# dc_dc_2.net
KiCad netlist of a schematic drawn in EAGLE
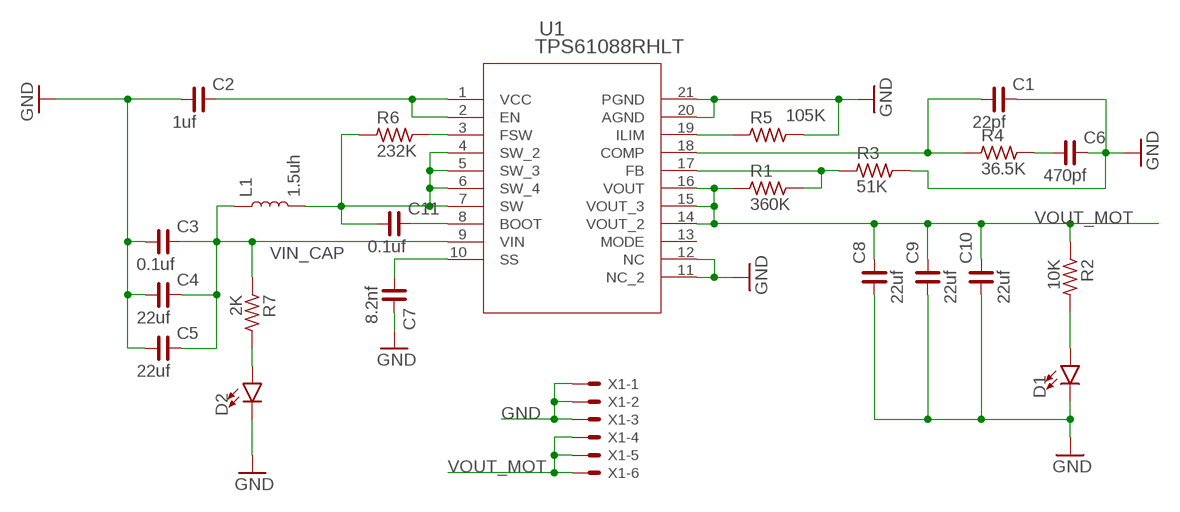
[diagram p0: schematic, sheet 1]

(export (version "E")
  (design (tool "Eeschema 10.0.6"))
  (components
    (comp (ref "C1")
      (value "22pf")
      (footprint "eagle-import:C0603")
      (libsource (lib "eagle-import") (part "C_0603"))
    )
    (comp (ref "C2")
      (value "1uf")
      (footprint "eagle-import:C0603")
      (libsource (lib "eagle-import") (part "C_0603"))
    )
    (comp (ref "C3")
      (value "0.1uf")
      (footprint "eagle-import:C1210")
      (libsource (lib "eagle-import") (part "C_1210"))
    )
    (comp (ref "C4")
      (value "22uf")
      (footprint "eagle-import:C1210")
      (libsource (lib "eagle-import") (part "C_1210"))
    )
    (comp (ref "C5")
      (value "22uf")
      (footprint "eagle-import:C1210")
      (libsource (lib "eagle-import") (part "C_1210"))
    )
    (comp (ref "C6")
      (value "470pf")
      (footprint "eagle-import:C0603")
      (libsource (lib "eagle-import") (part "C_0603"))
    )
    (comp (ref "C7")
      (value "8.2nf")
      (footprint "eagle-import:C0603")
      (libsource (lib "eagle-import") (part "C_0603"))
    )
    (comp (ref "C8")
      (value "22uf")
      (footprint "eagle-import:C1210")
      (libsource (lib "eagle-import") (part "C_1210"))
    )
    (comp (ref "C9")
      (value "22uf")
      (footprint "eagle-import:C1210")
      (libsource (lib "eagle-import") (part "C_1210"))
    )
    (comp (ref "C10")
      (value "22uf")
      (footprint "eagle-import:C1210")
      (libsource (lib "eagle-import") (part "C_1210"))
    )
    (comp (ref "C11")
      (value "0.1uf")
      (footprint "eagle-import:C0603")
      (libsource (lib "eagle-import") (part "C_0603"))
    )
    (comp (ref "D1")
      (value "LED0603")
      (footprint "eagle-import:LED-0603")
      (libsource (lib "eagle-import") (part "LED0603"))
    )
    (comp (ref "D2")
      (value "LED0603")
      (footprint "eagle-import:LED-0603")
      (libsource (lib "eagle-import") (part "LED0603"))
    )
    (comp (ref "L1")
      (value "1.5uh")
      (footprint "eagle-import:CR75")
      (libsource (lib "eagle-import") (part "INDUCTOR-CR75-68UH"))
    )
    (comp (ref "R1")
      (value "360K")
      (footprint "eagle-import:R0603")
      (libsource (lib "eagle-import") (part "R_0603"))
    )
    (comp (ref "R2")
      (value "10K")
      (footprint "eagle-import:R0603")
      (libsource (lib "eagle-import") (part "R_0603"))
    )
    (comp (ref "R3")
      (value "51K")
      (footprint "eagle-import:R0603")
      (libsource (lib "eagle-import") (part "R_0603"))
    )
    (comp (ref "R4")
      (value "36.5K")
      (footprint "eagle-import:R0603")
      (libsource (lib "eagle-import") (part "R_0603"))
    )
    (comp (ref "R5")
      (value "105K")
      (footprint "eagle-import:R0603")
      (libsource (lib "eagle-import") (part "R_0603"))
    )
    (comp (ref "R6")
      (value "232K")
      (footprint "eagle-import:R0603")
      (libsource (lib "eagle-import") (part "R_0603"))
    )
    (comp (ref "R7")
      (value "2K")
      (footprint "eagle-import:R0603")
      (libsource (lib "eagle-import") (part "R_0603"))
    )
    (comp (ref "U1")
      (value "TPS61088RHLT")
      (footprint "eagle-import:RHL0020A_TEX")
      (fields (field (name "COPYRIGHT") "Copyright (C) 2018 Accelerated Designs. All rights reserved"))
      (libsource (lib "eagle-import") (part "TPS61088RHLT"))
    )
    (comp (ref "X1")
      (value "22-23-2061")
      (footprint "eagle-import:22-23-2061")
      (fields (field (name "MF") "MOLEX"))
      (libsource (lib "eagle-import") (part "22-23-2061"))
    )
  )
  (nets
    (net (code "1") (name "/VIN_CAP") (class "Default")
      (node (ref "C3") (pin "2") (pinfunction "2_2") (pintype "passive"))
      (node (ref "C4") (pin "2") (pinfunction "2_2") (pintype "passive"))
      (node (ref "C5") (pin "2") (pinfunction "2_2") (pintype "passive"))
      (node (ref "L1") (pin "P$1") (pinfunction "1_P$1") (pintype "passive"))
      (node (ref "R7") (pin "1") (pinfunction "1_1") (pintype "passive"))
      (node (ref "U1") (pin "9") (pinfunction "VIN_9") (pintype "power_in"))
    )
    (net (code "2") (name "/VOUT_MOT") (class "Default")
      (node (ref "C10") (pin "2") (pinfunction "2_2") (pintype "passive"))
      (node (ref "C8") (pin "2") (pinfunction "2_2") (pintype "passive"))
      (node (ref "C9") (pin "2") (pinfunction "2_2") (pintype "passive"))
      (node (ref "R1") (pin "1") (pinfunction "1_1") (pintype "passive"))
      (node (ref "R2") (pin "1") (pinfunction "1_1") (pintype "passive"))
      (node (ref "U1") (pin "14") (pinfunction "VOUT_2_14") (pintype "power_in"))
      (node (ref "U1") (pin "15") (pinfunction "VOUT_3_15") (pintype "power_in"))
      (node (ref "U1") (pin "16") (pinfunction "VOUT_16") (pintype "power_in"))
      (node (ref "X1") (pin "4") (pinfunction "S_4") (pintype "passive"))
      (node (ref "X1") (pin "5") (pinfunction "S_5") (pintype "passive"))
      (node (ref "X1") (pin "6") (pinfunction "S_6") (pintype "passive"))
    )
    (net (code "3") (name "GND") (class "Default")
      (node (ref "C1") (pin "2") (pinfunction "2_2") (pintype "passive"))
      (node (ref "C10") (pin "1") (pinfunction "1_1") (pintype "passive"))
      (node (ref "C2") (pin "1") (pinfunction "1_1") (pintype "passive"))
      (node (ref "C3") (pin "1") (pinfunction "1_1") (pintype "passive"))
      (node (ref "C4") (pin "1") (pinfunction "1_1") (pintype "passive"))
      (node (ref "C5") (pin "1") (pinfunction "1_1") (pintype "passive"))
      (node (ref "C6") (pin "2") (pinfunction "2_2") (pintype "passive"))
      (node (ref "C7") (pin "2") (pinfunction "2_2") (pintype "passive"))
      (node (ref "C8") (pin "1") (pinfunction "1_1") (pintype "passive"))
      (node (ref "C9") (pin "1") (pinfunction "1_1") (pintype "passive"))
      (node (ref "D1") (pin "C") (pinfunction "C_C") (pintype "passive"))
      (node (ref "D2") (pin "C") (pinfunction "C_C") (pintype "passive"))
      (node (ref "R3") (pin "2") (pinfunction "2_2") (pintype "passive"))
      (node (ref "R5") (pin "2") (pinfunction "2_2") (pintype "passive"))
      (node (ref "U1") (pin "11") (pinfunction "NC_2_11") (pintype "passive"))
      (node (ref "U1") (pin "12") (pinfunction "NC_12") (pintype "passive"))
      (node (ref "U1") (pin "20") (pinfunction "AGND_20") (pintype "power_in"))
      (node (ref "U1") (pin "21") (pinfunction "PGND_21") (pintype "power_in"))
      (node (ref "X1") (pin "1") (pinfunction "S_1") (pintype "passive"))
      (node (ref "X1") (pin "2") (pinfunction "S_2") (pintype "passive"))
      (node (ref "X1") (pin "3") (pinfunction "S_3") (pintype "passive"))
    )
    (net (code "4") (name "Net-(C6-Pad1)") (class "Default")
      (node (ref "C6") (pin "1") (pinfunction "1_1") (pintype "passive"))
      (node (ref "R4") (pin "2") (pinfunction "2_2") (pintype "passive"))
    )
    (net (code "5") (name "Net-(D1-PadA)") (class "Default")
      (node (ref "D1") (pin "A") (pinfunction "A_A") (pintype "passive"))
      (node (ref "R2") (pin "2") (pinfunction "2_2") (pintype "passive"))
    )
    (net (code "6") (name "Net-(D2-PadA)") (class "Default")
      (node (ref "D2") (pin "A") (pinfunction "A_A") (pintype "passive"))
      (node (ref "R7") (pin "2") (pinfunction "2_2") (pintype "passive"))
    )
    (net (code "7") (name "Net-(L1-2)") (class "Default")
      (node (ref "C11") (pin "1") (pinfunction "1_1") (pintype "passive"))
      (node (ref "L1") (pin "P$2") (pinfunction "2_P$2") (pintype "passive"))
      (node (ref "R6") (pin "1") (pinfunction "1_1") (pintype "passive"))
      (node (ref "U1") (pin "4") (pinfunction "SW_2_4") (pintype "power_in"))
      (node (ref "U1") (pin "5") (pinfunction "SW_3_5") (pintype "power_in"))
      (node (ref "U1") (pin "6") (pinfunction "SW_4_6") (pintype "power_in"))
      (node (ref "U1") (pin "7") (pinfunction "SW_7") (pintype "power_in"))
    )
    (net (code "8") (name "Net-(U1-BOOT)") (class "Default")
      (node (ref "C11") (pin "2") (pinfunction "2_2") (pintype "passive"))
      (node (ref "U1") (pin "8") (pinfunction "BOOT_8") (pintype "power_in"))
    )
    (net (code "9") (name "Net-(U1-COMP)") (class "Default")
      (node (ref "C1") (pin "1") (pinfunction "1_1") (pintype "passive"))
      (node (ref "R4") (pin "1") (pinfunction "1_1") (pintype "passive"))
      (node (ref "U1") (pin "18") (pinfunction "COMP_18") (pintype "output"))
    )
    (net (code "10") (name "Net-(U1-EN)") (class "Default")
      (node (ref "C2") (pin "2") (pinfunction "2_2") (pintype "passive"))
      (node (ref "U1") (pin "1") (pinfunction "VCC_1") (pintype "power_in"))
      (node (ref "U1") (pin "2") (pinfunction "EN_2") (pintype "input"))
    )
    (net (code "11") (name "Net-(U1-FB)") (class "Default")
      (node (ref "R1") (pin "2") (pinfunction "2_2") (pintype "passive"))
      (node (ref "R3") (pin "1") (pinfunction "1_1") (pintype "passive"))
      (node (ref "U1") (pin "17") (pinfunction "FB_17") (pintype "input"))
    )
    (net (code "12") (name "Net-(U1-FSW)") (class "Default")
      (node (ref "R6") (pin "2") (pinfunction "2_2") (pintype "passive"))
      (node (ref "U1") (pin "3") (pinfunction "FSW_3") (pintype "input"))
    )
    (net (code "13") (name "Net-(U1-ILIM)") (class "Default")
      (node (ref "R5") (pin "1") (pinfunction "1_1") (pintype "passive"))
      (node (ref "U1") (pin "19") (pinfunction "ILIM_19") (pintype "input"))
    )
    (net (code "14") (name "Net-(U1-SS)") (class "Default")
      (node (ref "C7") (pin "1") (pinfunction "1_1") (pintype "passive"))
      (node (ref "U1") (pin "10") (pinfunction "SS_10") (pintype "input"))
    )
    (net (code "15") (name "unconnected-(U1-MODE-Pad13)") (class "Default")
      (node (ref "U1") (pin "13") (pinfunction "MODE_13") (pintype "input"))
    )
  )
)
